# MA600_Angle_Encoder.net
KiCad netlist of a schematic drawn in Altium Designer
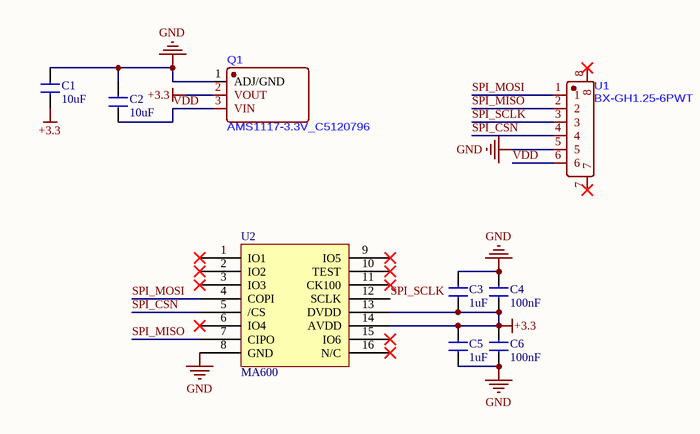
[diagram p0: MA600_Angle_Encoder.SchDoc]

(export (version "E")
  (design (tool "Eeschema 10.0.6"))
  (components
    (comp (ref "C1")
      (value "10uF")
      (footprint "1210")
      (description "1210贴片电容")
      (libsource (lib "En") (part "1210贴片电容"))
    )
    (comp (ref "C2")
      (value "10uF")
      (footprint "1210")
      (description "1210贴片电容")
      (libsource (lib "En") (part "1210贴片电容"))
    )
    (comp (ref "C3")
      (value "1uF")
      (footprint "C0402")
      (description "贴片电容0402")
      (libsource (lib "Integrated_Library1") (part "0402贴片电容"))
    )
    (comp (ref "C4")
      (value "100nF")
      (footprint "C0402")
      (description "贴片电容0402")
      (libsource (lib "Integrated_Library1") (part "0402贴片电容"))
    )
    (comp (ref "C5")
      (value "1uF")
      (footprint "C0402")
      (description "贴片电容0402")
      (libsource (lib "Integrated_Library1") (part "0402贴片电容"))
    )
    (comp (ref "C6")
      (value "100nF")
      (footprint "C0402")
      (description "贴片电容0402")
      (libsource (lib "Integrated_Library1") (part "0402贴片电容"))
    )
    (comp (ref "Q1")
      (value "AMS1117-3.3V_C5120796")
      (footprint "SOT-89-3_L4.5-W2.5-P1.50-LS4.2-BR")
      (libsource (lib "FOC_DRV8323") (part "AMS1117-3.3V_C5120796"))
    )
    (comp (ref "U1")
      (value "BX-GH1.25-6PWT")
      (footprint "CONN-SMD_6P-P1.25_BX-GH1.25-6PWT")
      (libsource (lib "MT6816_Angle_Encoder") (part "BX-GH1.25-6PWT"))
    )
    (comp (ref "U2")
      (value "MA600")
      (footprint "qfn-16-l3.0-w3.0-p0.50-tl-ep1.7")
      (description "磁编码器")
      (libsource (lib "Integrated_Library1") (part "MA600"))
    )
  )
  (nets
    (net (code "1") (name "+3.3") (class "Default")
      (node (ref "C1") (pin "1") (pinfunction "1_1") (pintype "passive"))
      (node (ref "C3") (pin "1") (pinfunction "1_1") (pintype "passive"))
      (node (ref "C4") (pin "1") (pinfunction "1_1") (pintype "passive"))
      (node (ref "C5") (pin "2") (pinfunction "2_2") (pintype "passive"))
      (node (ref "C6") (pin "2") (pinfunction "2_2") (pintype "passive"))
      (node (ref "Q1") (pin "2") (pinfunction "VOUT_2") (pintype "passive"))
      (node (ref "U2") (pin "13") (pinfunction "DVDD_13") (pintype "passive"))
      (node (ref "U2") (pin "14") (pinfunction "AVDD_14") (pintype "passive"))
    )
    (net (code "2") (name "/SPI_CSN") (class "Default")
      (node (ref "U1") (pin "4") (pinfunction "4_4") (pintype "passive"))
      (node (ref "U2") (pin "5") (pinfunction "/CS_5") (pintype "passive"))
    )
    (net (code "3") (name "/SPI_MISO") (class "Default")
      (node (ref "U1") (pin "2") (pinfunction "2_2") (pintype "passive"))
      (node (ref "U2") (pin "7") (pinfunction "CIPO_7") (pintype "passive"))
    )
    (net (code "4") (name "/SPI_MOSI") (class "Default")
      (node (ref "U1") (pin "1") (pinfunction "1_1") (pintype "passive"))
      (node (ref "U2") (pin "4") (pinfunction "COPI_4") (pintype "passive"))
    )
    (net (code "5") (name "/SPI_SCLK") (class "Default")
      (node (ref "U1") (pin "3") (pinfunction "3_3") (pintype "passive"))
      (node (ref "U2") (pin "12") (pinfunction "SCLK_12") (pintype "passive"))
    )
    (net (code "6") (name "/VDD") (class "Default")
      (node (ref "C2") (pin "1") (pinfunction "1_1") (pintype "passive"))
      (node (ref "Q1") (pin "3") (pinfunction "VIN_3") (pintype "passive"))
      (node (ref "U1") (pin "6") (pinfunction "6_6") (pintype "passive"))
    )
    (net (code "7") (name "GND") (class "Default")
      (node (ref "C1") (pin "2") (pinfunction "2_2") (pintype "passive"))
      (node (ref "C2") (pin "2") (pinfunction "2_2") (pintype "passive"))
      (node (ref "C3") (pin "2") (pinfunction "2_2") (pintype "passive"))
      (node (ref "C4") (pin "2") (pinfunction "2_2") (pintype "passive"))
      (node (ref "C5") (pin "1") (pinfunction "1_1") (pintype "passive"))
      (node (ref "C6") (pin "1") (pinfunction "1_1") (pintype "passive"))
      (node (ref "Q1") (pin "1") (pinfunction "ADJ/GND_1") (pintype "passive"))
      (node (ref "U1") (pin "5") (pinfunction "5_5") (pintype "passive"))
      (node (ref "U2") (pin "8") (pinfunction "GND_8") (pintype "passive"))
    )
    (net (code "8") (name "unconnected-(U1-Pad7)") (class "Default")
      (node (ref "U1") (pin "7") (pinfunction "7_7") (pintype "passive+no_connect"))
    )
    (net (code "9") (name "unconnected-(U1-Pad8)") (class "Default")
      (node (ref "U1") (pin "8") (pinfunction "8_8") (pintype "passive+no_connect"))
    )
    (net (code "10") (name "unconnected-(U2-CK100-Pad11)") (class "Default")
      (node (ref "U2") (pin "11") (pinfunction "CK100_11") (pintype "passive+no_connect"))
    )
    (net (code "11") (name "unconnected-(U2-IO1-Pad1)") (class "Default")
      (node (ref "U2") (pin "1") (pinfunction "IO1_1") (pintype "passive+no_connect"))
    )
    (net (code "12") (name "unconnected-(U2-IO2-Pad2)") (class "Default")
      (node (ref "U2") (pin "2") (pinfunction "IO2_2") (pintype "passive+no_connect"))
    )
    (net (code "13") (name "unconnected-(U2-IO3-Pad3)") (class "Default")
      (node (ref "U2") (pin "3") (pinfunction "IO3_3") (pintype "passive+no_connect"))
    )
    (net (code "14") (name "unconnected-(U2-IO4-Pad6)") (class "Default")
      (node (ref "U2") (pin "6") (pinfunction "IO4_6") (pintype "passive+no_connect"))
    )
    (net (code "15") (name "unconnected-(U2-IO5-Pad9)") (class "Default")
      (node (ref "U2") (pin "9") (pinfunction "IO5_9") (pintype "passive+no_connect"))
    )
    (net (code "16") (name "unconnected-(U2-IO6-Pad15)") (class "Default")
      (node (ref "U2") (pin "15") (pinfunction "IO6_15") (pintype "passive+no_connect"))
    )
    (net (code "17") (name "unconnected-(U2-N{slash}C-Pad16)") (class "Default")
      (node (ref "U2") (pin "16") (pinfunction "N/C_16") (pintype "passive+no_connect"))
    )
    (net (code "18") (name "unconnected-(U2-TEST-Pad10)") (class "Default")
      (node (ref "U2") (pin "10") (pinfunction "TEST_10") (pintype "passive+no_connect"))
    )
  )
)
